# Capteur_Main_P2.net
KiCad netlist of a schematic drawn in EasyEDA
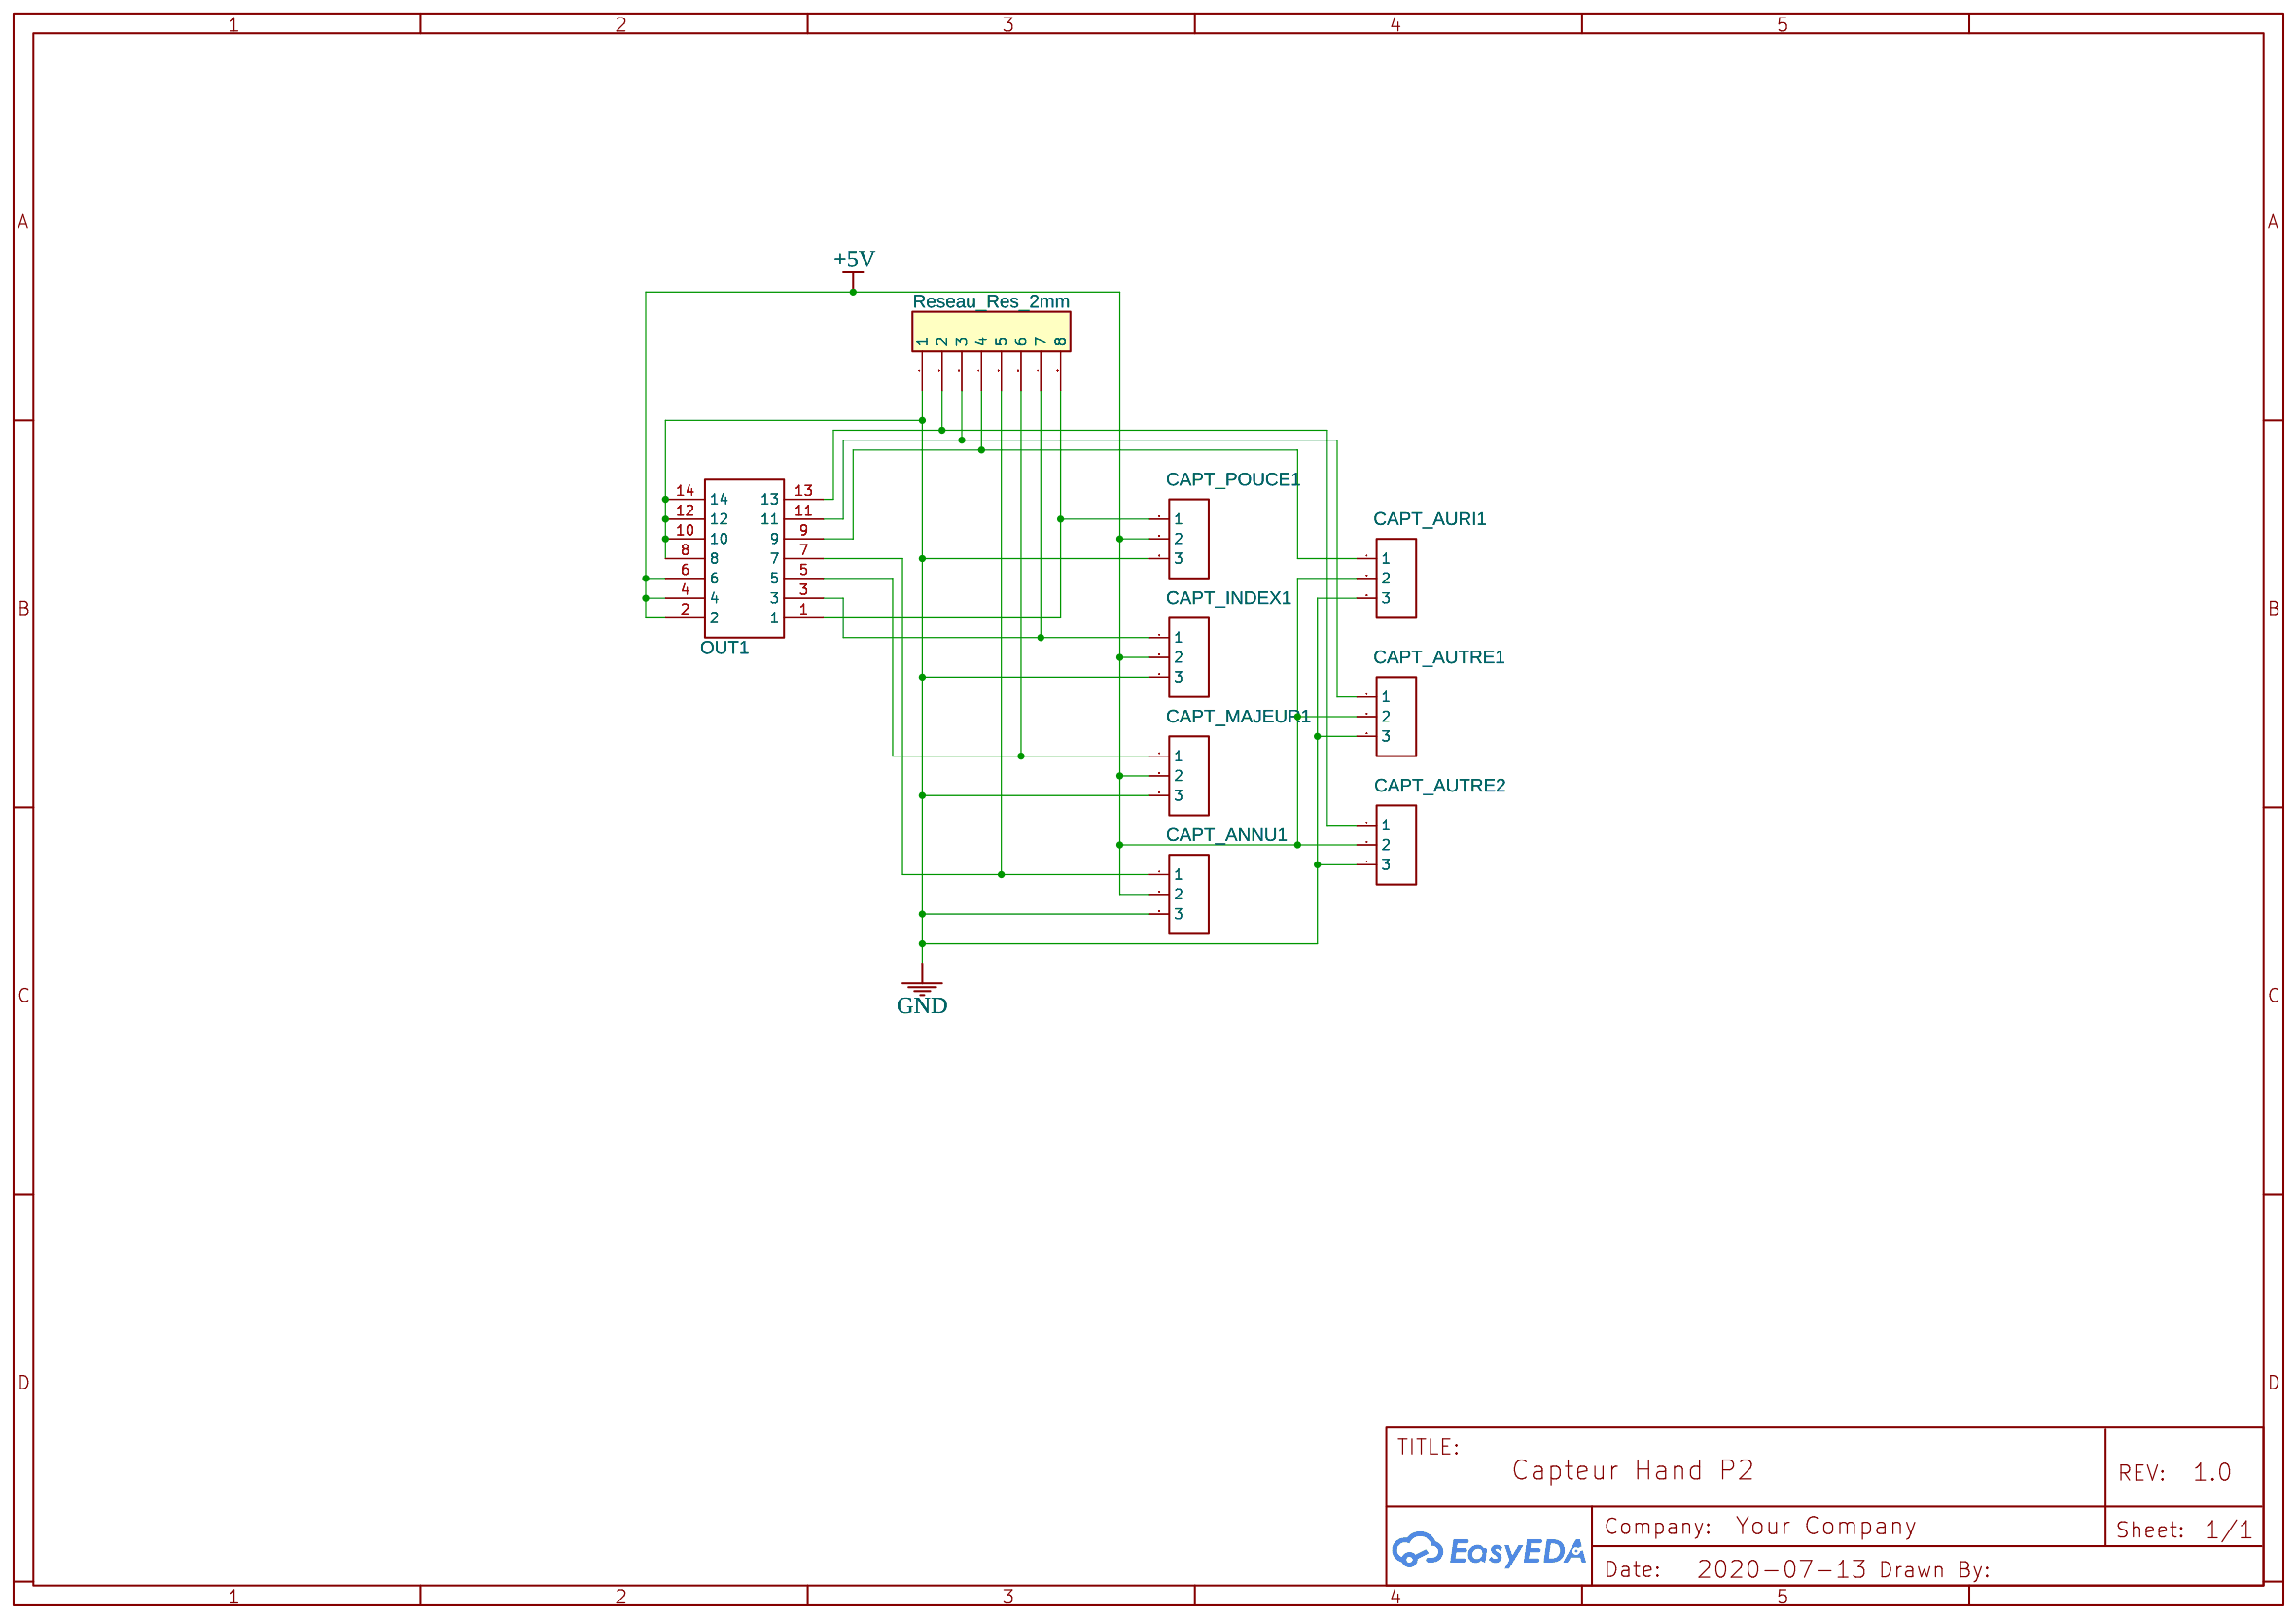
[diagram p0: schematic sheet]

(export (version "E")
  (design (tool "Eeschema 10.0.6"))
  (components
    (comp (ref "CAPT_ANNU1")
      (value "1")
      (fields
        (field (name "BOM_Manufacturer Part") "Header2.54mm 1*3P")
        (field (name "BOM_Supplier Part") "C49257")
      )
      (libsource (lib "") (part "Header-Male-2.54_1x3_3"))
    )
    (comp (ref "CAPT_AURI1")
      (value "1")
      (fields
        (field (name "BOM_Manufacturer Part") "Header2.54mm 1*3P")
        (field (name "BOM_Supplier Part") "C49257")
      )
      (libsource (lib "") (part "Header-Male-2.54_1x3_5"))
    )
    (comp (ref "CAPT_AUTRE1")
      (value "1")
      (fields
        (field (name "BOM_Manufacturer Part") "Header2.54mm 1*3P")
        (field (name "BOM_Supplier Part") "C49257")
      )
      (libsource (lib "") (part "Header-Male-2.54_1x3_4"))
    )
    (comp (ref "CAPT_AUTRE2")
      (value "1")
      (fields
        (field (name "BOM_Manufacturer Part") "Header2.54mm 1*3P")
        (field (name "BOM_Supplier Part") "C49257")
      )
      (libsource (lib "") (part "Header-Male-2.54_1x3_4"))
    )
    (comp (ref "CAPT_INDEX1")
      (value "1")
      (fields
        (field (name "BOM_Manufacturer Part") "Header2.54mm 1*3P")
        (field (name "BOM_Supplier Part") "C49257")
      )
      (libsource (lib "") (part "Header-Male-2.54_1x3"))
    )
    (comp (ref "CAPT_MAJEUR1")
      (value "1")
      (fields
        (field (name "BOM_Manufacturer Part") "Header2.54mm 1*3P")
        (field (name "BOM_Supplier Part") "C49257")
      )
      (libsource (lib "") (part "Header-Male-2.54_1x3_2"))
    )
    (comp (ref "CAPT_POUCE1")
      (value "1")
      (fields
        (field (name "BOM_Manufacturer Part") "Header2.54mm 1*3P")
        (field (name "BOM_Supplier Part") "C49257")
      )
      (libsource (lib "") (part "Header-Male-2.54_1x3_1"))
    )
    (comp (ref "OUT1")
      (value "Horn connector/2.0mm2*7P")
      (fields
        (field (name "BOM_Manufacturer Part") "Horn connector/2.0mm2*7P直简牛")
        (field (name "BOM_Supplier Part") "C29428")
      )
      (libsource (lib "") (part "Horn connector/2.0mm2*7P"))
    )
    (comp (ref "P1") (value "Reseau_Res_2mm") (libsource (lib "") (part "Reseau7R_2mm")))
  )
  (nets
    (net (code "1") (name "+5V") (class "Default")
      (node (ref "CAPT_ANNU1") (pin "2") (pinfunction "2_2") (pintype "input"))
      (node (ref "CAPT_AURI1") (pin "2") (pinfunction "2_2") (pintype "input"))
      (node (ref "CAPT_AUTRE1") (pin "2") (pinfunction "2_2") (pintype "input"))
      (node (ref "CAPT_AUTRE2") (pin "2") (pinfunction "2_2") (pintype "input"))
      (node (ref "CAPT_INDEX1") (pin "2") (pinfunction "2_2") (pintype "input"))
      (node (ref "CAPT_MAJEUR1") (pin "2") (pinfunction "2_2") (pintype "input"))
      (node (ref "CAPT_POUCE1") (pin "2") (pinfunction "2_2") (pintype "input"))
      (node (ref "OUT1") (pin "2") (pinfunction "2_2") (pintype "unspecified"))
      (node (ref "OUT1") (pin "4") (pinfunction "4_4") (pintype "unspecified"))
      (node (ref "OUT1") (pin "6") (pinfunction "6_6") (pintype "unspecified"))
    )
    (net (code "2") (name "GND") (class "Default")
      (node (ref "CAPT_ANNU1") (pin "3") (pinfunction "3_3") (pintype "input"))
      (node (ref "CAPT_AURI1") (pin "3") (pinfunction "3_3") (pintype "input"))
      (node (ref "CAPT_AUTRE1") (pin "3") (pinfunction "3_3") (pintype "input"))
      (node (ref "CAPT_AUTRE2") (pin "3") (pinfunction "3_3") (pintype "input"))
      (node (ref "CAPT_INDEX1") (pin "3") (pinfunction "3_3") (pintype "input"))
      (node (ref "CAPT_MAJEUR1") (pin "3") (pinfunction "3_3") (pintype "input"))
      (node (ref "CAPT_POUCE1") (pin "3") (pinfunction "3_3") (pintype "input"))
      (node (ref "OUT1") (pin "10") (pinfunction "10_10") (pintype "unspecified"))
      (node (ref "OUT1") (pin "12") (pinfunction "12_12") (pintype "unspecified"))
      (node (ref "OUT1") (pin "14") (pinfunction "14_14") (pintype "unspecified"))
      (node (ref "OUT1") (pin "8") (pinfunction "8_8") (pintype "unspecified"))
      (node (ref "P1") (pin "1") (pinfunction "1_1") (pintype "input"))
    )
    (net (code "3") (name "Net-(CAPT_ANNU1-Pad1)") (class "Default")
      (node (ref "CAPT_ANNU1") (pin "1") (pinfunction "1_1") (pintype "input"))
      (node (ref "OUT1") (pin "7") (pinfunction "7_7") (pintype "unspecified"))
      (node (ref "P1") (pin "5") (pinfunction "5_5") (pintype "input"))
    )
    (net (code "4") (name "Net-(CAPT_AURI1-Pad1)") (class "Default")
      (node (ref "CAPT_AURI1") (pin "1") (pinfunction "1_1") (pintype "input"))
      (node (ref "OUT1") (pin "9") (pinfunction "9_9") (pintype "unspecified"))
      (node (ref "P1") (pin "4") (pinfunction "4_4") (pintype "input"))
    )
    (net (code "5") (name "Net-(CAPT_AUTRE1-Pad1)") (class "Default")
      (node (ref "CAPT_AUTRE1") (pin "1") (pinfunction "1_1") (pintype "input"))
      (node (ref "OUT1") (pin "11") (pinfunction "11_11") (pintype "unspecified"))
      (node (ref "P1") (pin "3") (pinfunction "3_3") (pintype "input"))
    )
    (net (code "6") (name "Net-(CAPT_AUTRE2-Pad1)") (class "Default")
      (node (ref "CAPT_AUTRE2") (pin "1") (pinfunction "1_1") (pintype "input"))
      (node (ref "OUT1") (pin "13") (pinfunction "13_13") (pintype "unspecified"))
      (node (ref "P1") (pin "2") (pinfunction "2_2") (pintype "input"))
    )
    (net (code "7") (name "Net-(CAPT_INDEX1-Pad1)") (class "Default")
      (node (ref "CAPT_INDEX1") (pin "1") (pinfunction "1_1") (pintype "input"))
      (node (ref "OUT1") (pin "3") (pinfunction "3_3") (pintype "unspecified"))
      (node (ref "P1") (pin "7") (pinfunction "7_7") (pintype "input"))
    )
    (net (code "8") (name "Net-(CAPT_MAJEUR1-Pad1)") (class "Default")
      (node (ref "CAPT_MAJEUR1") (pin "1") (pinfunction "1_1") (pintype "input"))
      (node (ref "OUT1") (pin "5") (pinfunction "5_5") (pintype "unspecified"))
      (node (ref "P1") (pin "6") (pinfunction "6_6") (pintype "input"))
    )
    (net (code "9") (name "Net-(CAPT_POUCE1-Pad1)") (class "Default")
      (node (ref "CAPT_POUCE1") (pin "1") (pinfunction "1_1") (pintype "input"))
      (node (ref "OUT1") (pin "1") (pinfunction "1_1") (pintype "unspecified"))
      (node (ref "P1") (pin "8") (pinfunction "8_8") (pintype "input"))
    )
  )
)
